# MCU.net
KiCad netlist of a schematic drawn in Altium Designer
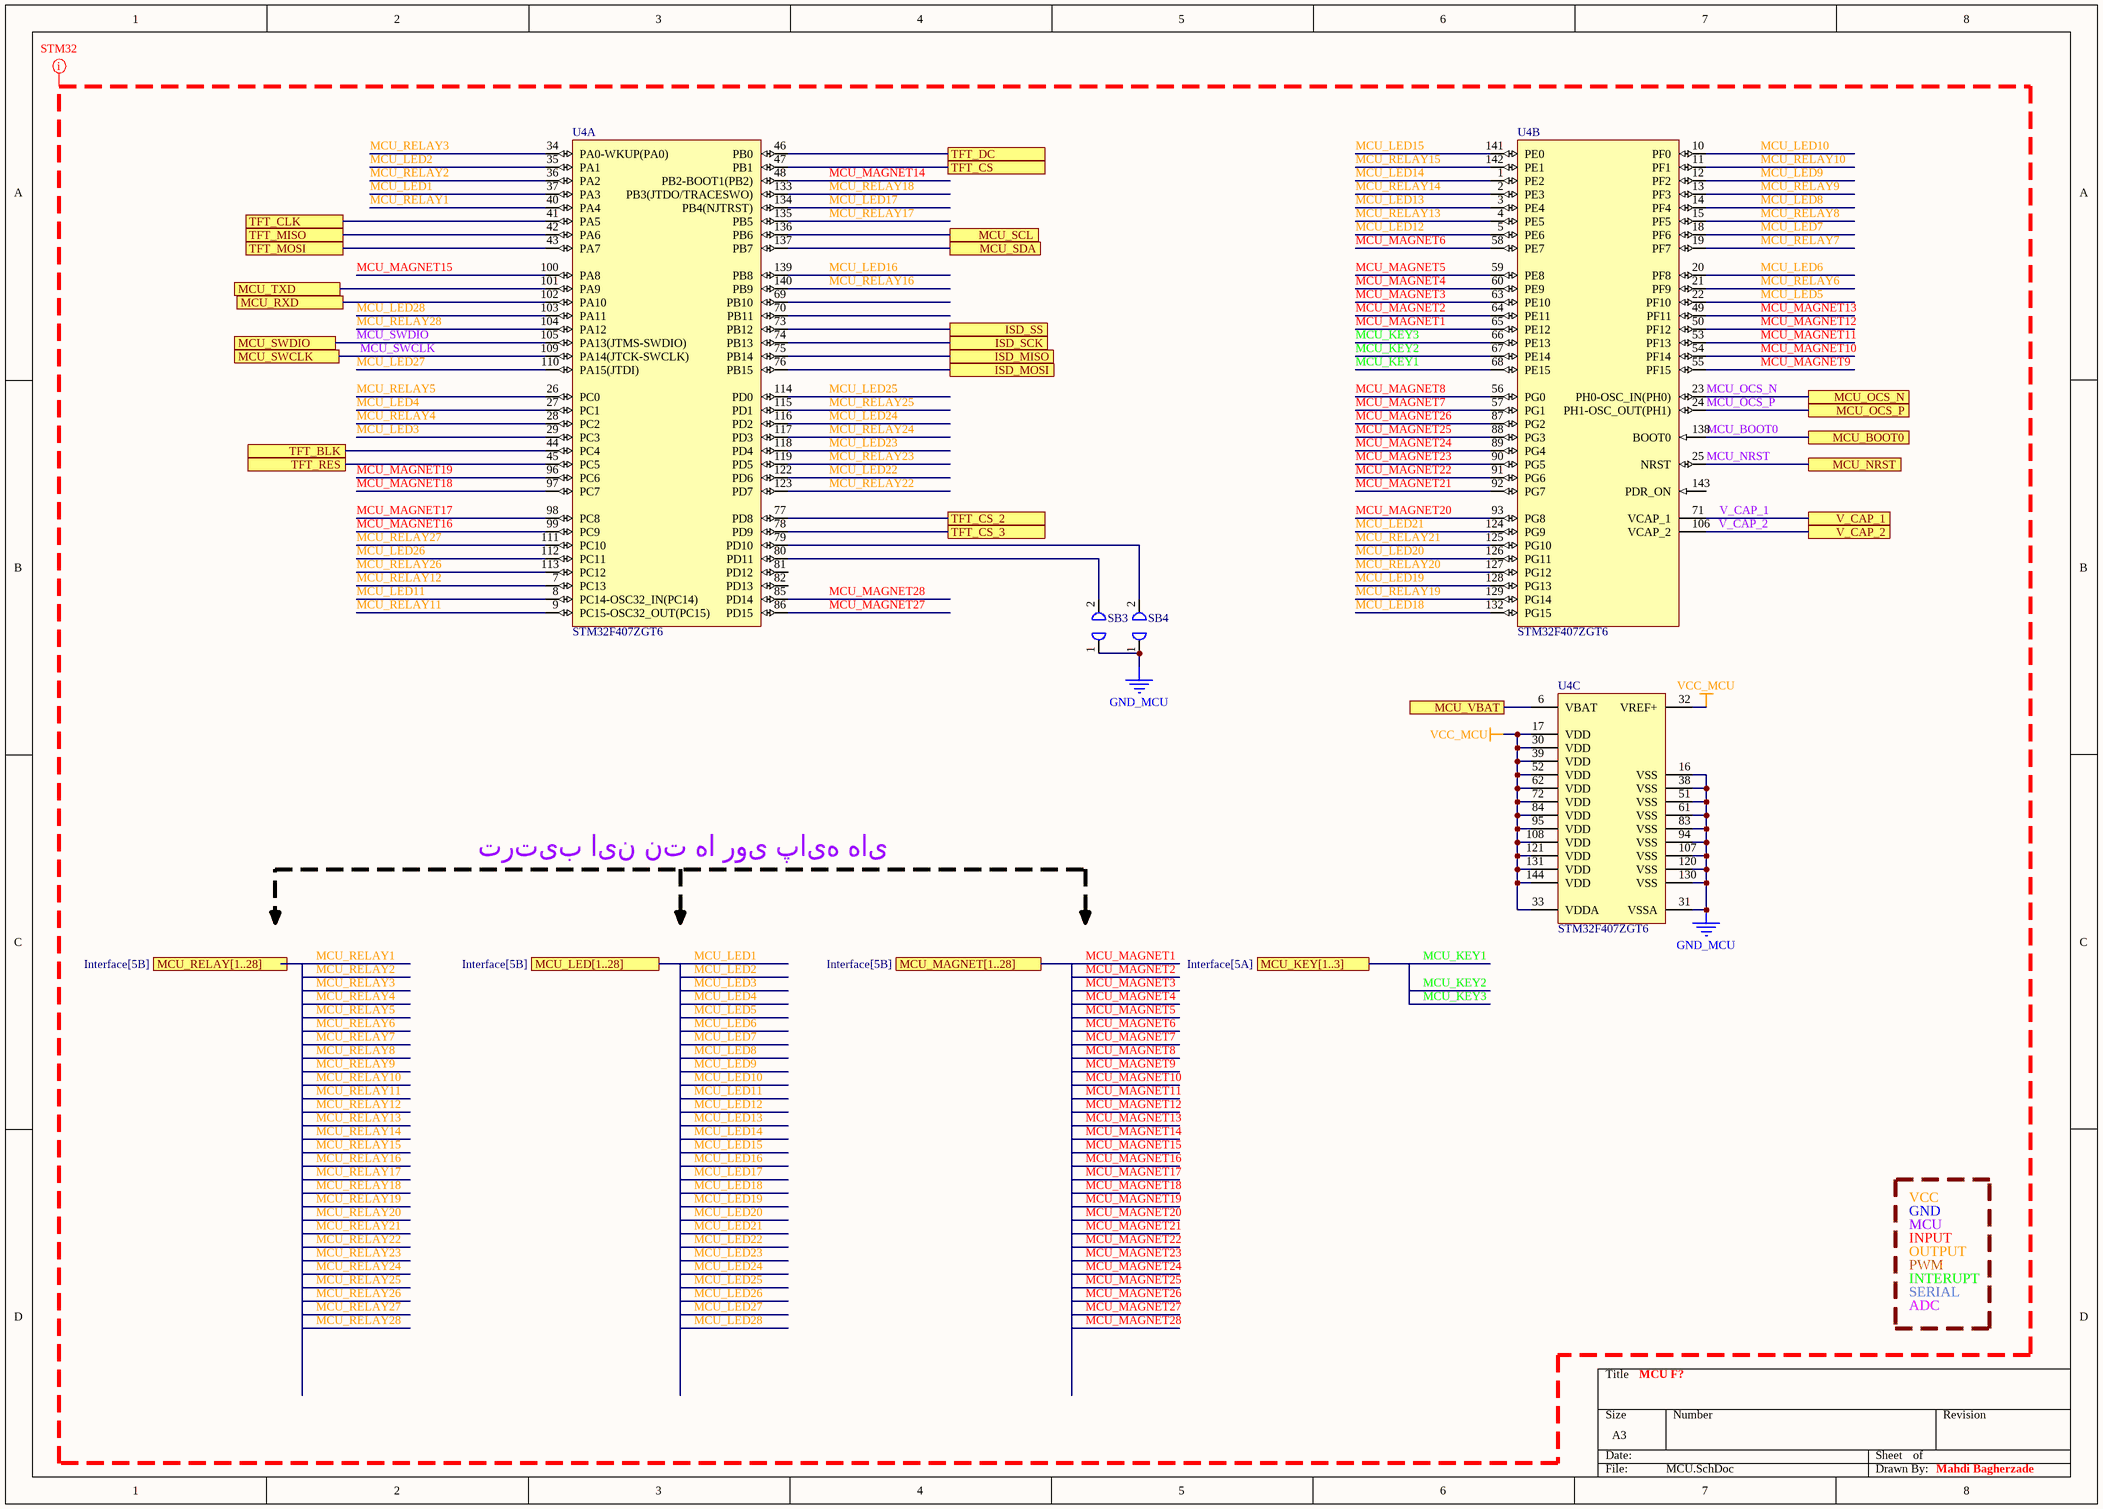
[diagram p0: MCU.SchDoc]

(export (version "E")
  (design (tool "Eeschema 10.0.6"))
  (components
    (comp (ref "SB3")
      (value "SOLDER BRIDGE-2")
      (footprint "SB-ARC")
      (fields (field (name "PUBLISHER") "Mahdi Bagherzadeh"))
      (libsource (lib "Mahdi-Bagherzadeh") (part "SOLDER BRIDGE-2"))
    )
    (comp (ref "SB4")
      (value "SOLDER BRIDGE-2")
      (footprint "SB-ARC")
      (fields (field (name "PUBLISHER") "Mahdi Bagherzadeh"))
      (libsource (lib "Mahdi-Bagherzadeh") (part "SOLDER BRIDGE-2"))
    )
    (comp (ref "U4")
      (value "STM32F407ZGT6")
      (footprint "STM-LQFP144_M")
      (fields (field (name "MANUFACTURER") "STMicroelectronics"))
      (libsource (lib "ST Microelectronics STM32 F4") (part "STM32F407ZGT6"))
    )
  )
  (nets
    (net (code "1") (name "/ISD_MISO") (class "Default")
      (node (ref "U4") (pin "75") (pinfunction "PB14_75") (pintype "bidirectional"))
    )
    (net (code "2") (name "/ISD_MOSI") (class "Default")
      (node (ref "U4") (pin "76") (pinfunction "PB15_76") (pintype "bidirectional"))
    )
    (net (code "3") (name "/ISD_SCK") (class "Default")
      (node (ref "U4") (pin "74") (pinfunction "PB13_74") (pintype "bidirectional"))
    )
    (net (code "4") (name "/ISD_SS") (class "Default")
      (node (ref "U4") (pin "73") (pinfunction "PB12_73") (pintype "bidirectional"))
    )
    (net (code "5") (name "/MCU_BOOT0") (class "Default")
      (node (ref "U4") (pin "138") (pinfunction "BOOT0_138") (pintype "input"))
    )
    (net (code "6") (name "/MCU_KEY1") (class "Default")
      (node (ref "U4") (pin "68") (pinfunction "PE15_68") (pintype "bidirectional"))
    )
    (net (code "7") (name "/MCU_KEY2") (class "Default")
      (node (ref "U4") (pin "67") (pinfunction "PE14_67") (pintype "bidirectional"))
    )
    (net (code "8") (name "/MCU_KEY3") (class "Default")
      (node (ref "U4") (pin "66") (pinfunction "PE13_66") (pintype "bidirectional"))
    )
    (net (code "10") (name "/MCU_LED1") (class "Default")
      (node (ref "U4") (pin "37") (pinfunction "PA3_37") (pintype "bidirectional"))
    )
    (net (code "11") (name "/MCU_LED2") (class "Default")
      (node (ref "U4") (pin "35") (pinfunction "PA1_35") (pintype "bidirectional"))
    )
    (net (code "12") (name "/MCU_LED3") (class "Default")
      (node (ref "U4") (pin "29") (pinfunction "PC3_29") (pintype "bidirectional"))
    )
    (net (code "13") (name "/MCU_LED4") (class "Default")
      (node (ref "U4") (pin "27") (pinfunction "PC1_27") (pintype "bidirectional"))
    )
    (net (code "14") (name "/MCU_LED5") (class "Default")
      (node (ref "U4") (pin "22") (pinfunction "PF10_22") (pintype "bidirectional"))
    )
    (net (code "15") (name "/MCU_LED6") (class "Default")
      (node (ref "U4") (pin "20") (pinfunction "PF8_20") (pintype "bidirectional"))
    )
    (net (code "16") (name "/MCU_LED7") (class "Default")
      (node (ref "U4") (pin "18") (pinfunction "PF6_18") (pintype "bidirectional"))
    )
    (net (code "17") (name "/MCU_LED8") (class "Default")
      (node (ref "U4") (pin "14") (pinfunction "PF4_14") (pintype "bidirectional"))
    )
    (net (code "18") (name "/MCU_LED9") (class "Default")
      (node (ref "U4") (pin "12") (pinfunction "PF2_12") (pintype "bidirectional"))
    )
    (net (code "19") (name "/MCU_LED10") (class "Default")
      (node (ref "U4") (pin "10") (pinfunction "PF0_10") (pintype "bidirectional"))
    )
    (net (code "20") (name "/MCU_LED11") (class "Default")
      (node (ref "U4") (pin "8") (pinfunction "PC14-OSC32_IN(PC14)_8") (pintype "bidirectional"))
    )
    (net (code "21") (name "/MCU_LED12") (class "Default")
      (node (ref "U4") (pin "5") (pinfunction "PE6_5") (pintype "bidirectional"))
    )
    (net (code "22") (name "/MCU_LED13") (class "Default")
      (node (ref "U4") (pin "3") (pinfunction "PE4_3") (pintype "bidirectional"))
    )
    (net (code "23") (name "/MCU_LED14") (class "Default")
      (node (ref "U4") (pin "1") (pinfunction "PE2_1") (pintype "bidirectional"))
    )
    (net (code "24") (name "/MCU_LED15") (class "Default")
      (node (ref "U4") (pin "141") (pinfunction "PE0_141") (pintype "bidirectional"))
    )
    (net (code "25") (name "/MCU_LED16") (class "Default")
      (node (ref "U4") (pin "139") (pinfunction "PB8_139") (pintype "bidirectional"))
    )
    (net (code "26") (name "/MCU_LED17") (class "Default")
      (node (ref "U4") (pin "134") (pinfunction "PB4(NJTRST)_134") (pintype "bidirectional"))
    )
    (net (code "27") (name "/MCU_LED18") (class "Default")
      (node (ref "U4") (pin "132") (pinfunction "PG15_132") (pintype "bidirectional"))
    )
    (net (code "28") (name "/MCU_LED19") (class "Default")
      (node (ref "U4") (pin "128") (pinfunction "PG13_128") (pintype "bidirectional"))
    )
    (net (code "29") (name "/MCU_LED20") (class "Default")
      (node (ref "U4") (pin "126") (pinfunction "PG11_126") (pintype "bidirectional"))
    )
    (net (code "30") (name "/MCU_LED21") (class "Default")
      (node (ref "U4") (pin "124") (pinfunction "PG9_124") (pintype "bidirectional"))
    )
    (net (code "31") (name "/MCU_LED22") (class "Default")
      (node (ref "U4") (pin "122") (pinfunction "PD6_122") (pintype "bidirectional"))
    )
    (net (code "32") (name "/MCU_LED23") (class "Default")
      (node (ref "U4") (pin "118") (pinfunction "PD4_118") (pintype "bidirectional"))
    )
    (net (code "33") (name "/MCU_LED24") (class "Default")
      (node (ref "U4") (pin "116") (pinfunction "PD2_116") (pintype "bidirectional"))
    )
    (net (code "34") (name "/MCU_LED25") (class "Default")
      (node (ref "U4") (pin "114") (pinfunction "PD0_114") (pintype "bidirectional"))
    )
    (net (code "35") (name "/MCU_LED26") (class "Default")
      (node (ref "U4") (pin "112") (pinfunction "PC11_112") (pintype "bidirectional"))
    )
    (net (code "36") (name "/MCU_LED27") (class "Default")
      (node (ref "U4") (pin "110") (pinfunction "PA15(JTDI)_110") (pintype "bidirectional"))
    )
    (net (code "37") (name "/MCU_LED28") (class "Default")
      (node (ref "U4") (pin "103") (pinfunction "PA11_103") (pintype "bidirectional"))
    )
    (net (code "39") (name "/MCU_MAGNET1") (class "Default")
      (node (ref "U4") (pin "65") (pinfunction "PE12_65") (pintype "bidirectional"))
    )
    (net (code "40") (name "/MCU_MAGNET2") (class "Default")
      (node (ref "U4") (pin "64") (pinfunction "PE11_64") (pintype "bidirectional"))
    )
    (net (code "41") (name "/MCU_MAGNET3") (class "Default")
      (node (ref "U4") (pin "63") (pinfunction "PE10_63") (pintype "bidirectional"))
    )
    (net (code "42") (name "/MCU_MAGNET4") (class "Default")
      (node (ref "U4") (pin "60") (pinfunction "PE9_60") (pintype "bidirectional"))
    )
    (net (code "43") (name "/MCU_MAGNET5") (class "Default")
      (node (ref "U4") (pin "59") (pinfunction "PE8_59") (pintype "bidirectional"))
    )
    (net (code "44") (name "/MCU_MAGNET6") (class "Default")
      (node (ref "U4") (pin "58") (pinfunction "PE7_58") (pintype "bidirectional"))
    )
    (net (code "45") (name "/MCU_MAGNET7") (class "Default")
      (node (ref "U4") (pin "57") (pinfunction "PG1_57") (pintype "bidirectional"))
    )
    (net (code "46") (name "/MCU_MAGNET8") (class "Default")
      (node (ref "U4") (pin "56") (pinfunction "PG0_56") (pintype "bidirectional"))
    )
    (net (code "47") (name "/MCU_MAGNET9") (class "Default")
      (node (ref "U4") (pin "55") (pinfunction "PF15_55") (pintype "bidirectional"))
    )
    (net (code "48") (name "/MCU_MAGNET10") (class "Default")
      (node (ref "U4") (pin "54") (pinfunction "PF14_54") (pintype "bidirectional"))
    )
    (net (code "49") (name "/MCU_MAGNET11") (class "Default")
      (node (ref "U4") (pin "53") (pinfunction "PF13_53") (pintype "bidirectional"))
    )
    (net (code "50") (name "/MCU_MAGNET12") (class "Default")
      (node (ref "U4") (pin "50") (pinfunction "PF12_50") (pintype "bidirectional"))
    )
    (net (code "51") (name "/MCU_MAGNET13") (class "Default")
      (node (ref "U4") (pin "49") (pinfunction "PF11_49") (pintype "bidirectional"))
    )
    (net (code "52") (name "/MCU_MAGNET14") (class "Default")
      (node (ref "U4") (pin "48") (pinfunction "PB2-BOOT1(PB2)_48") (pintype "bidirectional"))
    )
    (net (code "53") (name "/MCU_MAGNET15") (class "Default")
      (node (ref "U4") (pin "100") (pinfunction "PA8_100") (pintype "bidirectional"))
    )
    (net (code "54") (name "/MCU_MAGNET16") (class "Default")
      (node (ref "U4") (pin "99") (pinfunction "PC9_99") (pintype "bidirectional"))
    )
    (net (code "55") (name "/MCU_MAGNET17") (class "Default")
      (node (ref "U4") (pin "98") (pinfunction "PC8_98") (pintype "bidirectional"))
    )
    (net (code "56") (name "/MCU_MAGNET18") (class "Default")
      (node (ref "U4") (pin "97") (pinfunction "PC7_97") (pintype "bidirectional"))
    )
    (net (code "57") (name "/MCU_MAGNET19") (class "Default")
      (node (ref "U4") (pin "96") (pinfunction "PC6_96") (pintype "bidirectional"))
    )
    (net (code "58") (name "/MCU_MAGNET20") (class "Default")
      (node (ref "U4") (pin "93") (pinfunction "PG8_93") (pintype "bidirectional"))
    )
    (net (code "59") (name "/MCU_MAGNET21") (class "Default")
      (node (ref "U4") (pin "92") (pinfunction "PG7_92") (pintype "bidirectional"))
    )
    (net (code "60") (name "/MCU_MAGNET22") (class "Default")
      (node (ref "U4") (pin "91") (pinfunction "PG6_91") (pintype "bidirectional"))
    )
    (net (code "61") (name "/MCU_MAGNET23") (class "Default")
      (node (ref "U4") (pin "90") (pinfunction "PG5_90") (pintype "bidirectional"))
    )
    (net (code "62") (name "/MCU_MAGNET24") (class "Default")
      (node (ref "U4") (pin "89") (pinfunction "PG4_89") (pintype "bidirectional"))
    )
    (net (code "63") (name "/MCU_MAGNET25") (class "Default")
      (node (ref "U4") (pin "88") (pinfunction "PG3_88") (pintype "bidirectional"))
    )
    (net (code "64") (name "/MCU_MAGNET26") (class "Default")
      (node (ref "U4") (pin "87") (pinfunction "PG2_87") (pintype "bidirectional"))
    )
    (net (code "65") (name "/MCU_MAGNET27") (class "Default")
      (node (ref "U4") (pin "86") (pinfunction "PD15_86") (pintype "bidirectional"))
    )
    (net (code "66") (name "/MCU_MAGNET28") (class "Default")
      (node (ref "U4") (pin "85") (pinfunction "PD14_85") (pintype "bidirectional"))
    )
    (net (code "68") (name "/MCU_NRST") (class "Default")
      (node (ref "U4") (pin "25") (pinfunction "NRST_25") (pintype "bidirectional"))
    )
    (net (code "69") (name "/MCU_OCS_N") (class "Default")
      (node (ref "U4") (pin "23") (pinfunction "PH0-OSC_IN(PH0)_23") (pintype "bidirectional"))
    )
    (net (code "70") (name "/MCU_OCS_P") (class "Default")
      (node (ref "U4") (pin "24") (pinfunction "PH1-OSC_OUT(PH1)_24") (pintype "bidirectional"))
    )
    (net (code "71") (name "/MCU_RELAY1") (class "Default")
      (node (ref "U4") (pin "40") (pinfunction "PA4_40") (pintype "bidirectional"))
    )
    (net (code "72") (name "/MCU_RELAY2") (class "Default")
      (node (ref "U4") (pin "36") (pinfunction "PA2_36") (pintype "bidirectional"))
    )
    (net (code "73") (name "/MCU_RELAY3") (class "Default")
      (node (ref "U4") (pin "34") (pinfunction "PA0-WKUP(PA0)_34") (pintype "bidirectional"))
    )
    (net (code "74") (name "/MCU_RELAY4") (class "Default")
      (node (ref "U4") (pin "28") (pinfunction "PC2_28") (pintype "bidirectional"))
    )
    (net (code "75") (name "/MCU_RELAY5") (class "Default")
      (node (ref "U4") (pin "26") (pinfunction "PC0_26") (pintype "bidirectional"))
    )
    (net (code "76") (name "/MCU_RELAY6") (class "Default")
      (node (ref "U4") (pin "21") (pinfunction "PF9_21") (pintype "bidirectional"))
    )
    (net (code "77") (name "/MCU_RELAY7") (class "Default")
      (node (ref "U4") (pin "19") (pinfunction "PF7_19") (pintype "bidirectional"))
    )
    (net (code "78") (name "/MCU_RELAY8") (class "Default")
      (node (ref "U4") (pin "15") (pinfunction "PF5_15") (pintype "bidirectional"))
    )
    (net (code "79") (name "/MCU_RELAY9") (class "Default")
      (node (ref "U4") (pin "13") (pinfunction "PF3_13") (pintype "bidirectional"))
    )
    (net (code "80") (name "/MCU_RELAY10") (class "Default")
      (node (ref "U4") (pin "11") (pinfunction "PF1_11") (pintype "bidirectional"))
    )
    (net (code "81") (name "/MCU_RELAY11") (class "Default")
      (node (ref "U4") (pin "9") (pinfunction "PC15-OSC32_OUT(PC15)_9") (pintype "bidirectional"))
    )
    (net (code "82") (name "/MCU_RELAY12") (class "Default")
      (node (ref "U4") (pin "7") (pinfunction "PC13_7") (pintype "bidirectional"))
    )
    (net (code "83") (name "/MCU_RELAY13") (class "Default")
      (node (ref "U4") (pin "4") (pinfunction "PE5_4") (pintype "bidirectional"))
    )
    (net (code "84") (name "/MCU_RELAY14") (class "Default")
      (node (ref "U4") (pin "2") (pinfunction "PE3_2") (pintype "bidirectional"))
    )
    (net (code "85") (name "/MCU_RELAY15") (class "Default")
      (node (ref "U4") (pin "142") (pinfunction "PE1_142") (pintype "bidirectional"))
    )
    (net (code "86") (name "/MCU_RELAY16") (class "Default")
      (node (ref "U4") (pin "140") (pinfunction "PB9_140") (pintype "bidirectional"))
    )
    (net (code "87") (name "/MCU_RELAY17") (class "Default")
      (node (ref "U4") (pin "135") (pinfunction "PB5_135") (pintype "bidirectional"))
    )
    (net (code "88") (name "/MCU_RELAY18") (class "Default")
      (node (ref "U4") (pin "133") (pinfunction "PB3(JTDO/TRACESWO)_133") (pintype "bidirectional"))
    )
    (net (code "89") (name "/MCU_RELAY19") (class "Default")
      (node (ref "U4") (pin "129") (pinfunction "PG14_129") (pintype "bidirectional"))
    )
    (net (code "90") (name "/MCU_RELAY20") (class "Default")
      (node (ref "U4") (pin "127") (pinfunction "PG12_127") (pintype "bidirectional"))
    )
    (net (code "91") (name "/MCU_RELAY21") (class "Default")
      (node (ref "U4") (pin "125") (pinfunction "PG10_125") (pintype "bidirectional"))
    )
    (net (code "92") (name "/MCU_RELAY22") (class "Default")
      (node (ref "U4") (pin "123") (pinfunction "PD7_123") (pintype "bidirectional"))
    )
    (net (code "93") (name "/MCU_RELAY23") (class "Default")
      (node (ref "U4") (pin "119") (pinfunction "PD5_119") (pintype "bidirectional"))
    )
    (net (code "94") (name "/MCU_RELAY24") (class "Default")
      (node (ref "U4") (pin "117") (pinfunction "PD3_117") (pintype "bidirectional"))
    )
    (net (code "95") (name "/MCU_RELAY25") (class "Default")
      (node (ref "U4") (pin "115") (pinfunction "PD1_115") (pintype "bidirectional"))
    )
    (net (code "96") (name "/MCU_RELAY26") (class "Default")
      (node (ref "U4") (pin "113") (pinfunction "PC12_113") (pintype "bidirectional"))
    )
    (net (code "97") (name "/MCU_RELAY27") (class "Default")
      (node (ref "U4") (pin "111") (pinfunction "PC10_111") (pintype "bidirectional"))
    )
    (net (code "98") (name "/MCU_RELAY28") (class "Default")
      (node (ref "U4") (pin "104") (pinfunction "PA12_104") (pintype "bidirectional"))
    )
    (net (code "100") (name "/MCU_RXD") (class "Default")
      (node (ref "U4") (pin "102") (pinfunction "PA10_102") (pintype "bidirectional"))
    )
    (net (code "101") (name "/MCU_SCL") (class "Default")
      (node (ref "U4") (pin "136") (pinfunction "PB6_136") (pintype "bidirectional"))
    )
    (net (code "102") (name "/MCU_SDA") (class "Default")
      (node (ref "U4") (pin "137") (pinfunction "PB7_137") (pintype "bidirectional"))
    )
    (net (code "103") (name "/MCU_SWCLK") (class "Default")
      (node (ref "U4") (pin "109") (pinfunction "PA14(JTCK-SWCLK)_109") (pintype "bidirectional"))
    )
    (net (code "104") (name "/MCU_SWDIO") (class "Default")
      (node (ref "U4") (pin "105") (pinfunction "PA13(JTMS-SWDIO)_105") (pintype "bidirectional"))
    )
    (net (code "105") (name "/MCU_TXD") (class "Default")
      (node (ref "U4") (pin "101") (pinfunction "PA9_101") (pintype "bidirectional"))
    )
    (net (code "106") (name "/MCU_VBAT") (class "Default")
      (node (ref "U4") (pin "6") (pinfunction "VBAT_6") (pintype "power_in"))
    )
    (net (code "107") (name "/TFT_BLK") (class "Default")
      (node (ref "U4") (pin "44") (pinfunction "PC4_44") (pintype "bidirectional"))
    )
    (net (code "108") (name "/TFT_CLK") (class "Default")
      (node (ref "U4") (pin "41") (pinfunction "PA5_41") (pintype "bidirectional"))
    )
    (net (code "109") (name "/TFT_CS") (class "Default")
      (node (ref "U4") (pin "47") (pinfunction "PB1_47") (pintype "bidirectional"))
    )
    (net (code "110") (name "/TFT_CS_2") (class "Default")
      (node (ref "U4") (pin "77") (pinfunction "PD8_77") (pintype "bidirectional"))
    )
    (net (code "111") (name "/TFT_CS_3") (class "Default")
      (node (ref "U4") (pin "78") (pinfunction "PD9_78") (pintype "bidirectional"))
    )
    (net (code "112") (name "/TFT_DC") (class "Default")
      (node (ref "U4") (pin "46") (pinfunction "PB0_46") (pintype "bidirectional"))
    )
    (net (code "113") (name "/TFT_MISO") (class "Default")
      (node (ref "U4") (pin "42") (pinfunction "PA6_42") (pintype "bidirectional"))
    )
    (net (code "114") (name "/TFT_MOSI") (class "Default")
      (node (ref "U4") (pin "43") (pinfunction "PA7_43") (pintype "bidirectional"))
    )
    (net (code "115") (name "/TFT_RES") (class "Default")
      (node (ref "U4") (pin "45") (pinfunction "PC5_45") (pintype "bidirectional"))
    )
    (net (code "116") (name "/V_CAP_1") (class "Default")
      (node (ref "U4") (pin "71") (pinfunction "VCAP_1_71") (pintype "power_in"))
    )
    (net (code "117") (name "/V_CAP_2") (class "Default")
      (node (ref "U4") (pin "106") (pinfunction "VCAP_2_106") (pintype "power_in"))
    )
    (net (code "118") (name "GND_MCU") (class "Default")
      (node (ref "SB3") (pin "1") (pinfunction "1_1") (pintype "passive"))
      (node (ref "SB4") (pin "1") (pinfunction "1_1") (pintype "passive"))
      (node (ref "U4") (pin "107") (pinfunction "VSS_107") (pintype "power_in"))
      (node (ref "U4") (pin "120") (pinfunction "VSS_120") (pintype "power_in"))
      (node (ref "U4") (pin "130") (pinfunction "VSS_130") (pintype "power_in"))
      (node (ref "U4") (pin "16") (pinfunction "VSS_16") (pintype "power_in"))
      (node (ref "U4") (pin "31") (pinfunction "VSSA_31") (pintype "power_in"))
      (node (ref "U4") (pin "38") (pinfunction "VSS_38") (pintype "power_in"))
      (node (ref "U4") (pin "51") (pinfunction "VSS_51") (pintype "power_in"))
      (node (ref "U4") (pin "61") (pinfunction "VSS_61") (pintype "power_in"))
      (node (ref "U4") (pin "83") (pinfunction "VSS_83") (pintype "power_in"))
      (node (ref "U4") (pin "94") (pinfunction "VSS_94") (pintype "power_in"))
    )
    (net (code "119") (name "Net-(U4A-PD10)") (class "Default")
      (node (ref "SB4") (pin "2") (pinfunction "2_2") (pintype "passive"))
      (node (ref "U4") (pin "79") (pinfunction "PD10_79") (pintype "bidirectional"))
    )
    (net (code "120") (name "Net-(U4A-PD11)") (class "Default")
      (node (ref "SB3") (pin "2") (pinfunction "2_2") (pintype "passive"))
      (node (ref "U4") (pin "80") (pinfunction "PD11_80") (pintype "bidirectional"))
    )
    (net (code "121") (name "VCC_MCU") (class "Default")
      (node (ref "U4") (pin "108") (pinfunction "VDD_108") (pintype "power_in"))
      (node (ref "U4") (pin "121") (pinfunction "VDD_121") (pintype "power_in"))
      (node (ref "U4") (pin "131") (pinfunction "VDD_131") (pintype "power_in"))
      (node (ref "U4") (pin "144") (pinfunction "VDD_144") (pintype "power_in"))
      (node (ref "U4") (pin "17") (pinfunction "VDD_17") (pintype "power_in"))
      (node (ref "U4") (pin "30") (pinfunction "VDD_30") (pintype "power_in"))
      (node (ref "U4") (pin "32") (pinfunction "VREF+_32") (pintype "power_in"))
      (node (ref "U4") (pin "33") (pinfunction "VDDA_33") (pintype "power_in"))
      (node (ref "U4") (pin "39") (pinfunction "VDD_39") (pintype "power_in"))
      (node (ref "U4") (pin "52") (pinfunction "VDD_52") (pintype "power_in"))
      (node (ref "U4") (pin "62") (pinfunction "VDD_62") (pintype "power_in"))
      (node (ref "U4") (pin "72") (pinfunction "VDD_72") (pintype "power_in"))
      (node (ref "U4") (pin "84") (pinfunction "VDD_84") (pintype "power_in"))
      (node (ref "U4") (pin "95") (pinfunction "VDD_95") (pintype "power_in"))
    )
    (net (code "122") (name "unconnected-(U4A-PB10-Pad69)") (class "Default")
      (node (ref "U4") (pin "69") (pinfunction "PB10_69") (pintype "bidirectional"))
    )
    (net (code "123") (name "unconnected-(U4A-PB11-Pad70)") (class "Default")
      (node (ref "U4") (pin "70") (pinfunction "PB11_70") (pintype "bidirectional"))
    )
    (net (code "124") (name "unconnected-(U4A-PD12-Pad81)") (class "Default")
      (node (ref "U4") (pin "81") (pinfunction "PD12_81") (pintype "bidirectional"))
    )
    (net (code "125") (name "unconnected-(U4A-PD13-Pad82)") (class "Default")
      (node (ref "U4") (pin "82") (pinfunction "PD13_82") (pintype "bidirectional"))
    )
    (net (code "126") (name "unconnected-(U4B-PDR_ON-Pad143)") (class "Default")
      (node (ref "U4") (pin "143") (pinfunction "PDR_ON_143") (pintype "input"))
    )
  )
)
